# tftclock.net
KiCad netlist of a schematic drawn in EasyEDA
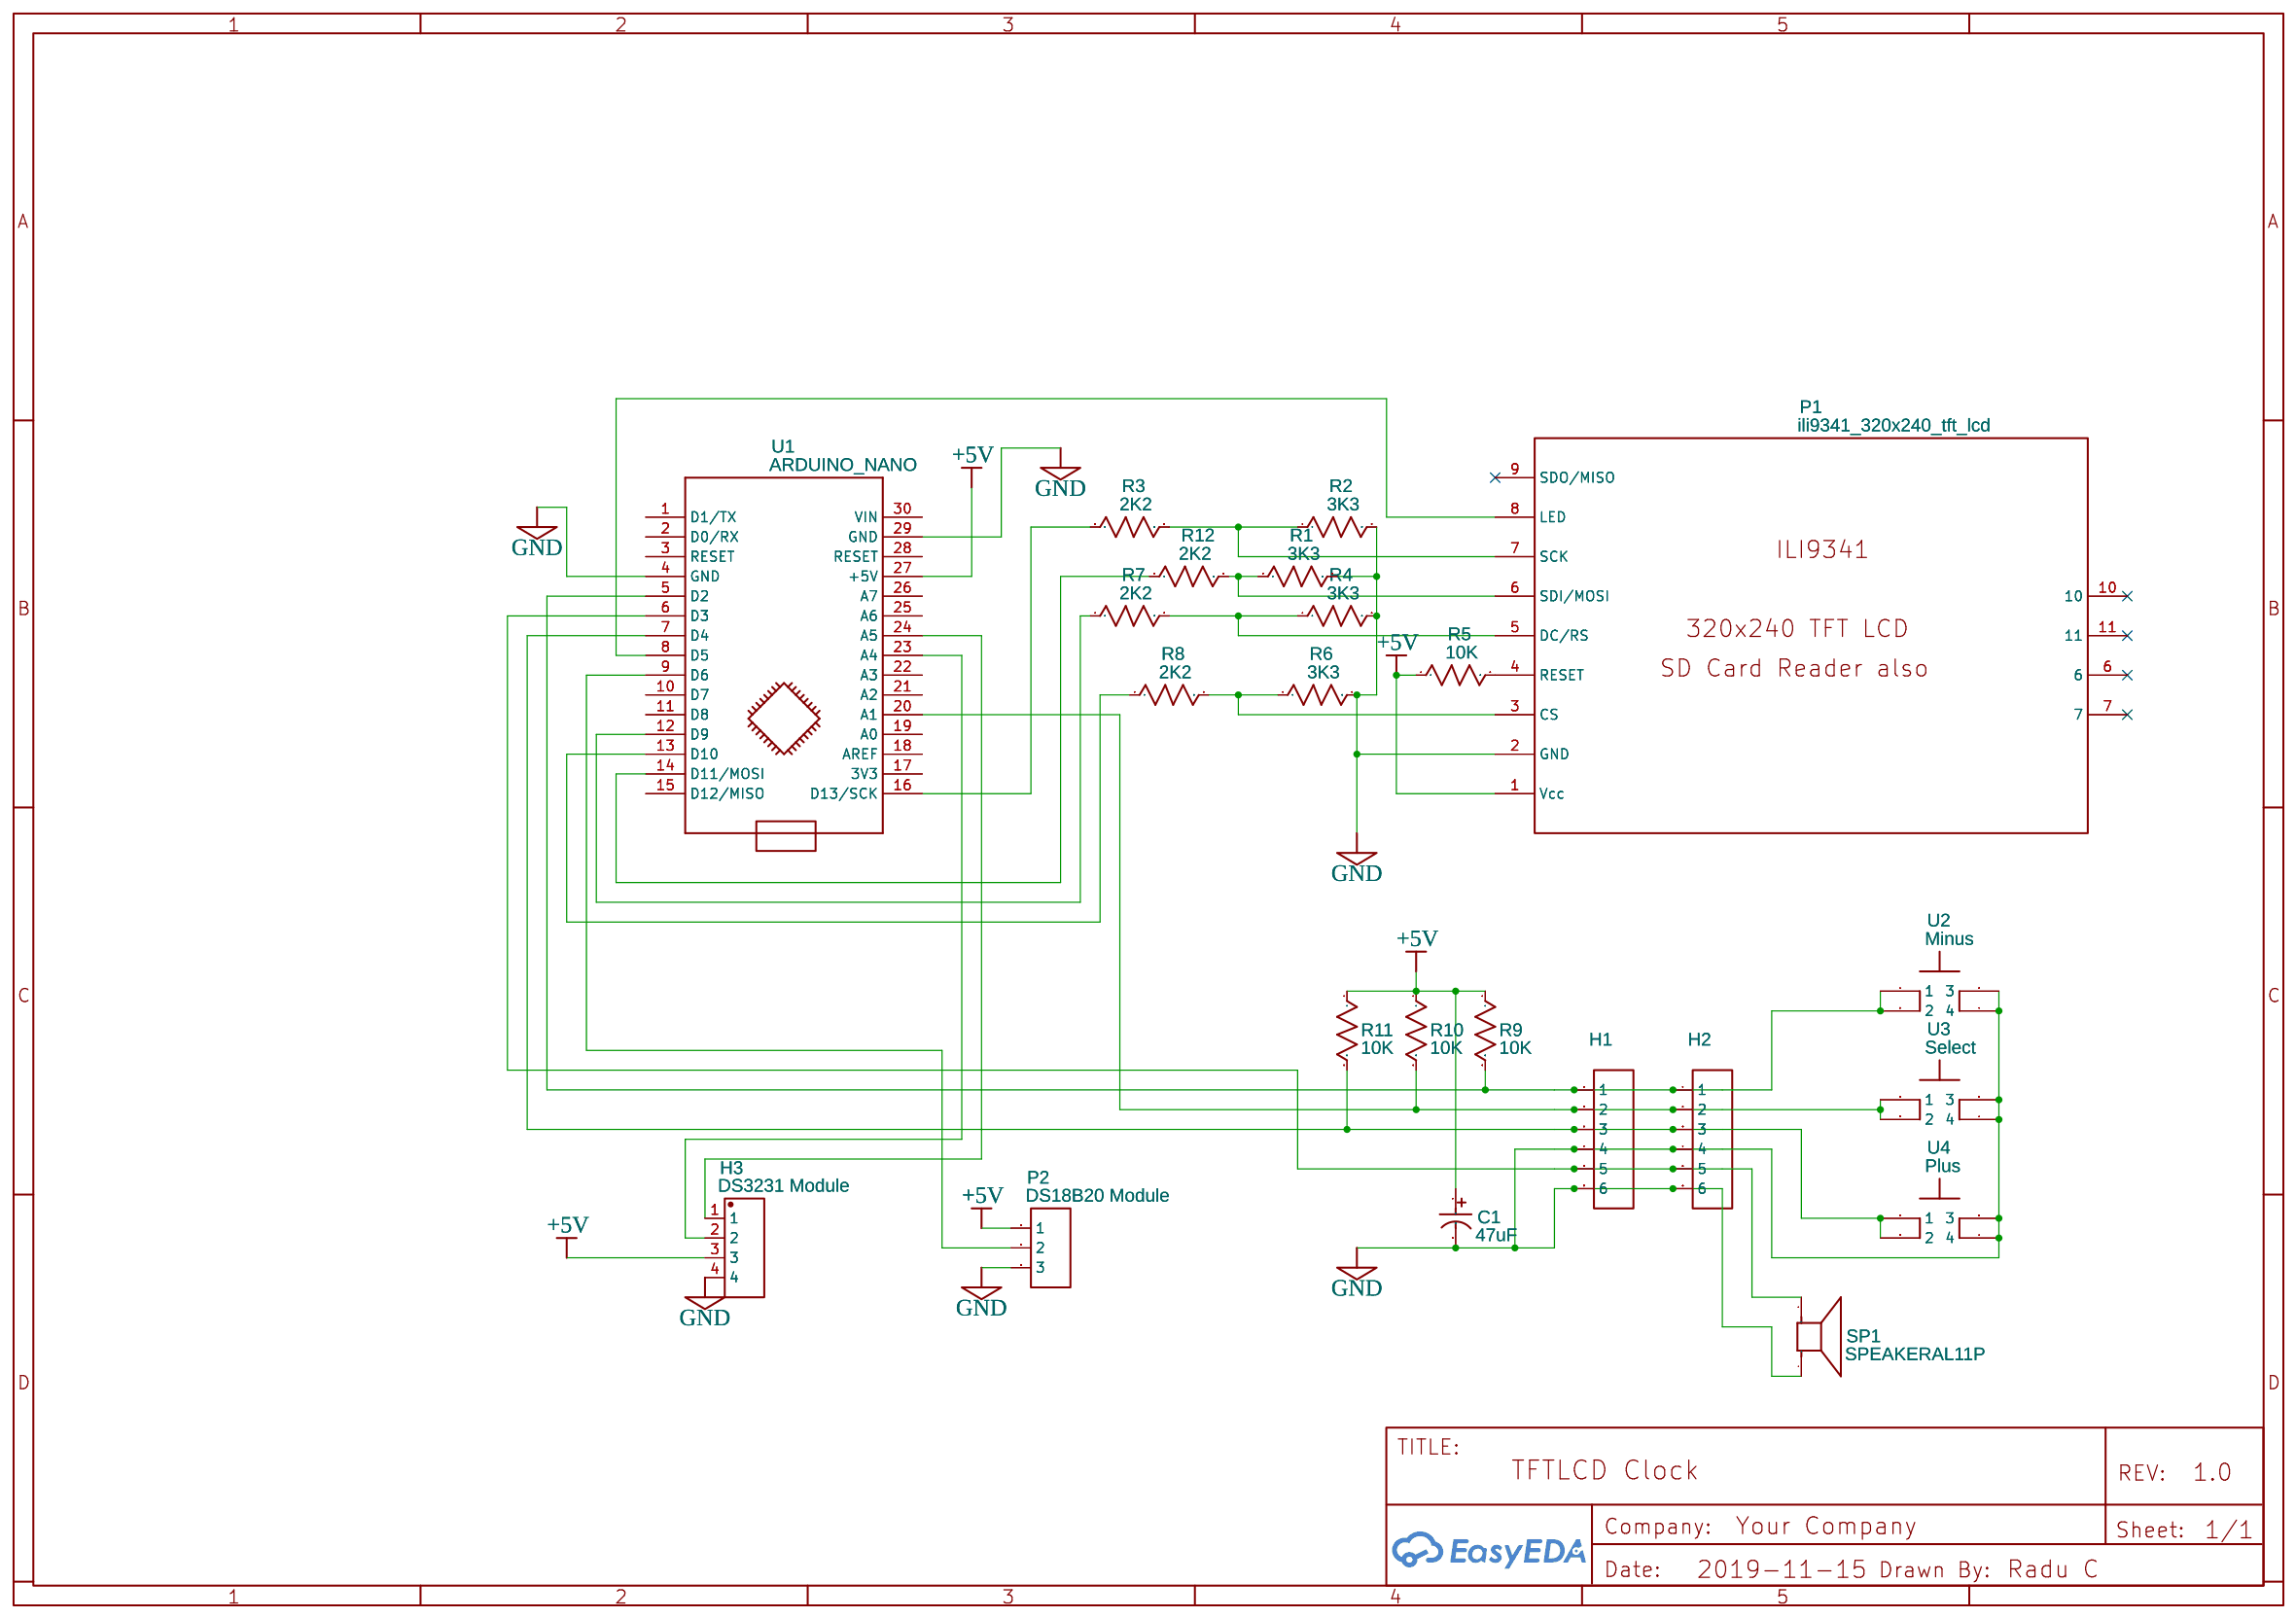
[diagram p0: schematic sheet]

(export (version "E")
  (design (tool "Eeschema 10.0.6"))
  (components
    (comp (ref "C1")
      (value "47uF")
      (fields
        (field (name "BOM_Manufacturer Part") "47uF 16V Aluminum electrolytic capacitors")
        (field (name "BOM_Supplier Part") "C22320")
      )
      (libsource (lib "") (part "47uF 16V Aluminum electrolytic capacitors"))
    )
    (comp (ref "H1")
      (value "H")
      (fields
        (field (name "BOM_Manufacturer Part") "Header-Male-2.54_1x6")
        (field (name "BOM_Supplier Part") "C37208")
      )
      (libsource (lib "") (part "Unknown_805_570"))
    )
    (comp (ref "H2")
      (value "Header-Male-2.54_1x6")
      (fields (field (name "BOM_Supplier Part") "C37208"))
      (libsource (lib "") (part "Unknown_855_570"))
    )
    (comp (ref "H3")
      (value "DS3231 Module")
      (fields
        (field (name "BOM_Manufacturer Part") "Headers  Pins 1*4P")
        (field (name "BOM_Supplier Part") "C59481")
      )
      (libsource (lib "") (part "Unknown_365_625"))
    )
    (comp (ref "P1") (value "ili9341_320x240_tft_lcd") (libsource (lib "") (part "Unknown_790_325")))
    (comp (ref "P2")
      (value "DS18B20 Module")
      (fields
        (field (name "BOM_Manufacturer Part") "Header-Female-2.54_1x3")
        (field (name "BOM_Supplier Part") "C146243")
      )
      (libsource (lib "") (part "Unknown_520_625"))
    )
    (comp (ref "R1") (value "3K3") (libsource (lib "") (part "1206_1")))
    (comp (ref "R2") (value "3K3") (libsource (lib "") (part "1206_1")))
    (comp (ref "R3") (value "2K2") (libsource (lib "") (part "1206_1")))
    (comp (ref "R4") (value "3K3") (libsource (lib "") (part "1206_1")))
    (comp (ref "R5") (value "10K") (libsource (lib "") (part "1206_1")))
    (comp (ref "R6") (value "3K3") (libsource (lib "") (part "1206_1")))
    (comp (ref "R7") (value "2K2") (libsource (lib "") (part "1206_1")))
    (comp (ref "R8") (value "2K2") (libsource (lib "") (part "1206_1")))
    (comp (ref "R9") (value "10K") (libsource (lib "") (part "1206")))
    (comp (ref "R10") (value "10K") (libsource (lib "") (part "1206")))
    (comp (ref "R11") (value "10K") (libsource (lib "") (part "1206")))
    (comp (ref "R12") (value "2K2") (libsource (lib "") (part "1206_1")))
    (comp (ref "SP1") (value "SPEAKERAL11P") (libsource (lib "") (part "Unknown_915_670")))
    (comp (ref "U1") (value "ARDUINO_NANO") (libsource (lib "") (part "Unknown_390_330")))
    (comp (ref "U2")
      (value "Minus")
      (fields (field (name "BOM_Manufacturer Part") "Pushbutton"))
      (libsource (lib "") (part "Unknown_975_495"))
    )
    (comp (ref "U3")
      (value "Select")
      (fields (field (name "BOM_Manufacturer Part") "Pushbutton"))
      (libsource (lib "") (part "Unknown_975_550"))
    )
    (comp (ref "U4")
      (value "Plus")
      (fields (field (name "BOM_Manufacturer Part") "Pushbutton"))
      (libsource (lib "") (part "Unknown_975_610"))
    )
  )
  (nets
    (net (code "1") (name "+5V") (class "Default")
      (node (ref "C1") (pin "1") (pinfunction "1_1") (pintype "input"))
      (node (ref "H3") (pin "3") (pinfunction "3_3") (pintype "unspecified"))
      (node (ref "P1") (pin "1") (pinfunction "Vcc_1") (pintype "passive"))
      (node (ref "P2") (pin "1") (pinfunction "1_1") (pintype "input"))
      (node (ref "R10") (pin "1") (pinfunction "1_1") (pintype "unspecified"))
      (node (ref "R11") (pin "1") (pinfunction "1_1") (pintype "unspecified"))
      (node (ref "R5") (pin "1") (pinfunction "1_1") (pintype "unspecified"))
      (node (ref "R9") (pin "1") (pinfunction "1_1") (pintype "unspecified"))
      (node (ref "U1") (pin "27") (pinfunction "+5V_27") (pintype "unspecified"))
    )
    (net (code "2") (name "GND") (class "Default")
      (node (ref "C1") (pin "2") (pinfunction "2_2") (pintype "input"))
      (node (ref "H1") (pin "4") (pinfunction "4_4") (pintype "input"))
      (node (ref "H1") (pin "6") (pinfunction "6_6") (pintype "input"))
      (node (ref "H2") (pin "4") (pinfunction "4_4") (pintype "input"))
      (node (ref "H2") (pin "6") (pinfunction "6_6") (pintype "input"))
      (node (ref "H3") (pin "4") (pinfunction "4_4") (pintype "unspecified"))
      (node (ref "P1") (pin "2") (pinfunction "GND_2") (pintype "passive"))
      (node (ref "P2") (pin "3") (pinfunction "3_3") (pintype "input"))
      (node (ref "R1") (pin "2") (pinfunction "2_2") (pintype "unspecified"))
      (node (ref "R2") (pin "2") (pinfunction "2_2") (pintype "unspecified"))
      (node (ref "R4") (pin "2") (pinfunction "2_2") (pintype "unspecified"))
      (node (ref "R6") (pin "2") (pinfunction "2_2") (pintype "unspecified"))
      (node (ref "SP1") (pin "-") (pinfunction "-_-") (pintype "unspecified"))
      (node (ref "U1") (pin "29") (pinfunction "GND_29") (pintype "unspecified"))
      (node (ref "U1") (pin "4") (pinfunction "GND_4") (pintype "unspecified"))
      (node (ref "U2") (pin "3") (pinfunction "3_3") (pintype "unspecified"))
      (node (ref "U2") (pin "4") (pinfunction "4_4") (pintype "unspecified"))
      (node (ref "U3") (pin "3") (pinfunction "3_3") (pintype "unspecified"))
      (node (ref "U3") (pin "4") (pinfunction "4_4") (pintype "unspecified"))
      (node (ref "U4") (pin "3") (pinfunction "3_3") (pintype "unspecified"))
      (node (ref "U4") (pin "4") (pinfunction "4_4") (pintype "unspecified"))
    )
    (net (code "3") (name "Net-(P1-CS)") (class "Default")
      (node (ref "P1") (pin "3") (pinfunction "CS_3") (pintype "input"))
      (node (ref "R6") (pin "1") (pinfunction "1_1") (pintype "unspecified"))
      (node (ref "R8") (pin "2") (pinfunction "2_2") (pintype "unspecified"))
    )
    (net (code "4") (name "Net-(P1-DC{slash}RS)") (class "Default")
      (node (ref "P1") (pin "5") (pinfunction "DC/RS_5") (pintype "input"))
      (node (ref "R4") (pin "1") (pinfunction "1_1") (pintype "unspecified"))
      (node (ref "R7") (pin "2") (pinfunction "2_2") (pintype "unspecified"))
    )
    (net (code "5") (name "Net-(P1-LED)") (class "Default")
      (node (ref "P1") (pin "8") (pinfunction "LED_8") (pintype "input"))
      (node (ref "U1") (pin "8") (pinfunction "D5_8") (pintype "unspecified"))
    )
    (net (code "6") (name "Net-(P1-RESET)") (class "Default")
      (node (ref "P1") (pin "4") (pinfunction "RESET_4") (pintype "input"))
      (node (ref "R5") (pin "2") (pinfunction "2_2") (pintype "unspecified"))
    )
    (net (code "7") (name "Net-(P1-SCK)") (class "Default")
      (node (ref "P1") (pin "7") (pinfunction "SCK_7") (pintype "input"))
      (node (ref "R2") (pin "1") (pinfunction "1_1") (pintype "unspecified"))
      (node (ref "R3") (pin "2") (pinfunction "2_2") (pintype "unspecified"))
    )
    (net (code "8") (name "Net-(P1-SDI{slash}MOSI)") (class "Default")
      (node (ref "P1") (pin "6") (pinfunction "SDI/MOSI_6") (pintype "input"))
      (node (ref "R1") (pin "1") (pinfunction "1_1") (pintype "unspecified"))
      (node (ref "R12") (pin "2") (pinfunction "2_2") (pintype "unspecified"))
    )
    (net (code "9") (name "Net-(U1-A1)") (class "Default")
      (node (ref "H1") (pin "2") (pinfunction "2_2") (pintype "input"))
      (node (ref "H2") (pin "2") (pinfunction "2_2") (pintype "input"))
      (node (ref "R10") (pin "2") (pinfunction "2_2") (pintype "unspecified"))
      (node (ref "U1") (pin "20") (pinfunction "A1_20") (pintype "unspecified"))
      (node (ref "U3") (pin "1") (pinfunction "1_1") (pintype "unspecified"))
      (node (ref "U3") (pin "2") (pinfunction "2_2") (pintype "unspecified"))
    )
    (net (code "10") (name "Net-(U1-A4)") (class "Default")
      (node (ref "H3") (pin "2") (pinfunction "2_2") (pintype "unspecified"))
      (node (ref "U1") (pin "23") (pinfunction "A4_23") (pintype "unspecified"))
    )
    (net (code "11") (name "Net-(U1-A5)") (class "Default")
      (node (ref "H3") (pin "1") (pinfunction "1_1") (pintype "unspecified"))
      (node (ref "U1") (pin "24") (pinfunction "A5_24") (pintype "unspecified"))
    )
    (net (code "12") (name "Net-(U1-D2)") (class "Default")
      (node (ref "H1") (pin "1") (pinfunction "1_1") (pintype "input"))
      (node (ref "H2") (pin "1") (pinfunction "1_1") (pintype "input"))
      (node (ref "R9") (pin "2") (pinfunction "2_2") (pintype "unspecified"))
      (node (ref "U1") (pin "5") (pinfunction "D2_5") (pintype "unspecified"))
      (node (ref "U2") (pin "1") (pinfunction "1_1") (pintype "unspecified"))
      (node (ref "U2") (pin "2") (pinfunction "2_2") (pintype "unspecified"))
    )
    (net (code "13") (name "Net-(U1-D3)") (class "Default")
      (node (ref "H1") (pin "5") (pinfunction "5_5") (pintype "input"))
      (node (ref "H2") (pin "5") (pinfunction "5_5") (pintype "input"))
      (node (ref "SP1") (pin "+") (pinfunction "+_+") (pintype "unspecified"))
      (node (ref "U1") (pin "6") (pinfunction "D3_6") (pintype "unspecified"))
    )
    (net (code "14") (name "Net-(U1-D4)") (class "Default")
      (node (ref "H1") (pin "3") (pinfunction "3_3") (pintype "input"))
      (node (ref "H2") (pin "3") (pinfunction "3_3") (pintype "input"))
      (node (ref "R11") (pin "2") (pinfunction "2_2") (pintype "unspecified"))
      (node (ref "U1") (pin "7") (pinfunction "D4_7") (pintype "unspecified"))
      (node (ref "U4") (pin "1") (pinfunction "1_1") (pintype "unspecified"))
      (node (ref "U4") (pin "2") (pinfunction "2_2") (pintype "unspecified"))
    )
    (net (code "15") (name "Net-(U1-D6)") (class "Default")
      (node (ref "P2") (pin "2") (pinfunction "2_2") (pintype "input"))
      (node (ref "U1") (pin "9") (pinfunction "D6_9") (pintype "unspecified"))
    )
    (net (code "16") (name "Net-(U1-D9)") (class "Default")
      (node (ref "R7") (pin "1") (pinfunction "1_1") (pintype "unspecified"))
      (node (ref "U1") (pin "12") (pinfunction "D9_12") (pintype "unspecified"))
    )
    (net (code "17") (name "Net-(U1-D10)") (class "Default")
      (node (ref "R8") (pin "1") (pinfunction "1_1") (pintype "unspecified"))
      (node (ref "U1") (pin "13") (pinfunction "D10_13") (pintype "unspecified"))
    )
    (net (code "18") (name "Net-(U1-D11{slash}MOSI)") (class "Default")
      (node (ref "R12") (pin "1") (pinfunction "1_1") (pintype "unspecified"))
      (node (ref "U1") (pin "14") (pinfunction "D11/MOSI_14") (pintype "unspecified"))
    )
    (net (code "19") (name "Net-(U1-D13{slash}SCK)") (class "Default")
      (node (ref "R3") (pin "1") (pinfunction "1_1") (pintype "unspecified"))
      (node (ref "U1") (pin "16") (pinfunction "D13/SCK_16") (pintype "unspecified"))
    )
    (net (code "20") (name "unconnected-(P1-Pad6)") (class "Default")
      (node (ref "P1") (pin "6") (pinfunction "6_6") (pintype "unspecified+no_connect"))
    )
    (net (code "21") (name "unconnected-(P1-Pad7)") (class "Default")
      (node (ref "P1") (pin "7") (pinfunction "7_7") (pintype "unspecified+no_connect"))
    )
    (net (code "22") (name "unconnected-(P1-Pad10)") (class "Default")
      (node (ref "P1") (pin "10") (pinfunction "10_10") (pintype "unspecified+no_connect"))
    )
    (net (code "23") (name "unconnected-(P1-Pad11)") (class "Default")
      (node (ref "P1") (pin "11") (pinfunction "11_11") (pintype "unspecified+no_connect"))
    )
    (net (code "24") (name "unconnected-(P1-SDO{slash}MISO-Pad9)") (class "Default")
      (node (ref "P1") (pin "9") (pinfunction "SDO/MISO_9") (pintype "output+no_connect"))
    )
    (net (code "25") (name "unconnected-(U1-3V3-Pad17)") (class "Default")
      (node (ref "U1") (pin "17") (pinfunction "3V3_17") (pintype "unspecified"))
    )
    (net (code "26") (name "unconnected-(U1-A0-Pad19)") (class "Default")
      (node (ref "U1") (pin "19") (pinfunction "A0_19") (pintype "unspecified"))
    )
    (net (code "27") (name "unconnected-(U1-A2-Pad21)") (class "Default")
      (node (ref "U1") (pin "21") (pinfunction "A2_21") (pintype "unspecified"))
    )
    (net (code "28") (name "unconnected-(U1-A3-Pad22)") (class "Default")
      (node (ref "U1") (pin "22") (pinfunction "A3_22") (pintype "unspecified"))
    )
    (net (code "29") (name "unconnected-(U1-A6-Pad25)") (class "Default")
      (node (ref "U1") (pin "25") (pinfunction "A6_25") (pintype "unspecified"))
    )
    (net (code "30") (name "unconnected-(U1-A7-Pad26)") (class "Default")
      (node (ref "U1") (pin "26") (pinfunction "A7_26") (pintype "unspecified"))
    )
    (net (code "31") (name "unconnected-(U1-AREF-Pad18)") (class "Default")
      (node (ref "U1") (pin "18") (pinfunction "AREF_18") (pintype "unspecified"))
    )
    (net (code "32") (name "unconnected-(U1-D0{slash}RX-Pad2)") (class "Default")
      (node (ref "U1") (pin "2") (pinfunction "D0/RX_2") (pintype "unspecified"))
    )
    (net (code "33") (name "unconnected-(U1-D1{slash}TX-Pad1)") (class "Default")
      (node (ref "U1") (pin "1") (pinfunction "D1/TX_1") (pintype "unspecified"))
    )
    (net (code "34") (name "unconnected-(U1-D7-Pad10)") (class "Default")
      (node (ref "U1") (pin "10") (pinfunction "D7_10") (pintype "unspecified"))
    )
    (net (code "35") (name "unconnected-(U1-D8-Pad11)") (class "Default")
      (node (ref "U1") (pin "11") (pinfunction "D8_11") (pintype "unspecified"))
    )
    (net (code "36") (name "unconnected-(U1-D12{slash}MISO-Pad15)") (class "Default")
      (node (ref "U1") (pin "15") (pinfunction "D12/MISO_15") (pintype "unspecified"))
    )
    (net (code "37") (name "unconnected-(U1-RESET-Pad3)") (class "Default")
      (node (ref "U1") (pin "3") (pinfunction "RESET_3") (pintype "unspecified"))
    )
    (net (code "38") (name "unconnected-(U1-RESET-Pad28)") (class "Default")
      (node (ref "U1") (pin "28") (pinfunction "RESET_28") (pintype "unspecified"))
    )
    (net (code "39") (name "unconnected-(U1-VIN-Pad30)") (class "Default")
      (node (ref "U1") (pin "30") (pinfunction "VIN_30") (pintype "unspecified"))
    )
  )
)
